# CONTROL.net
KiCad netlist of a schematic drawn in Altium Designer
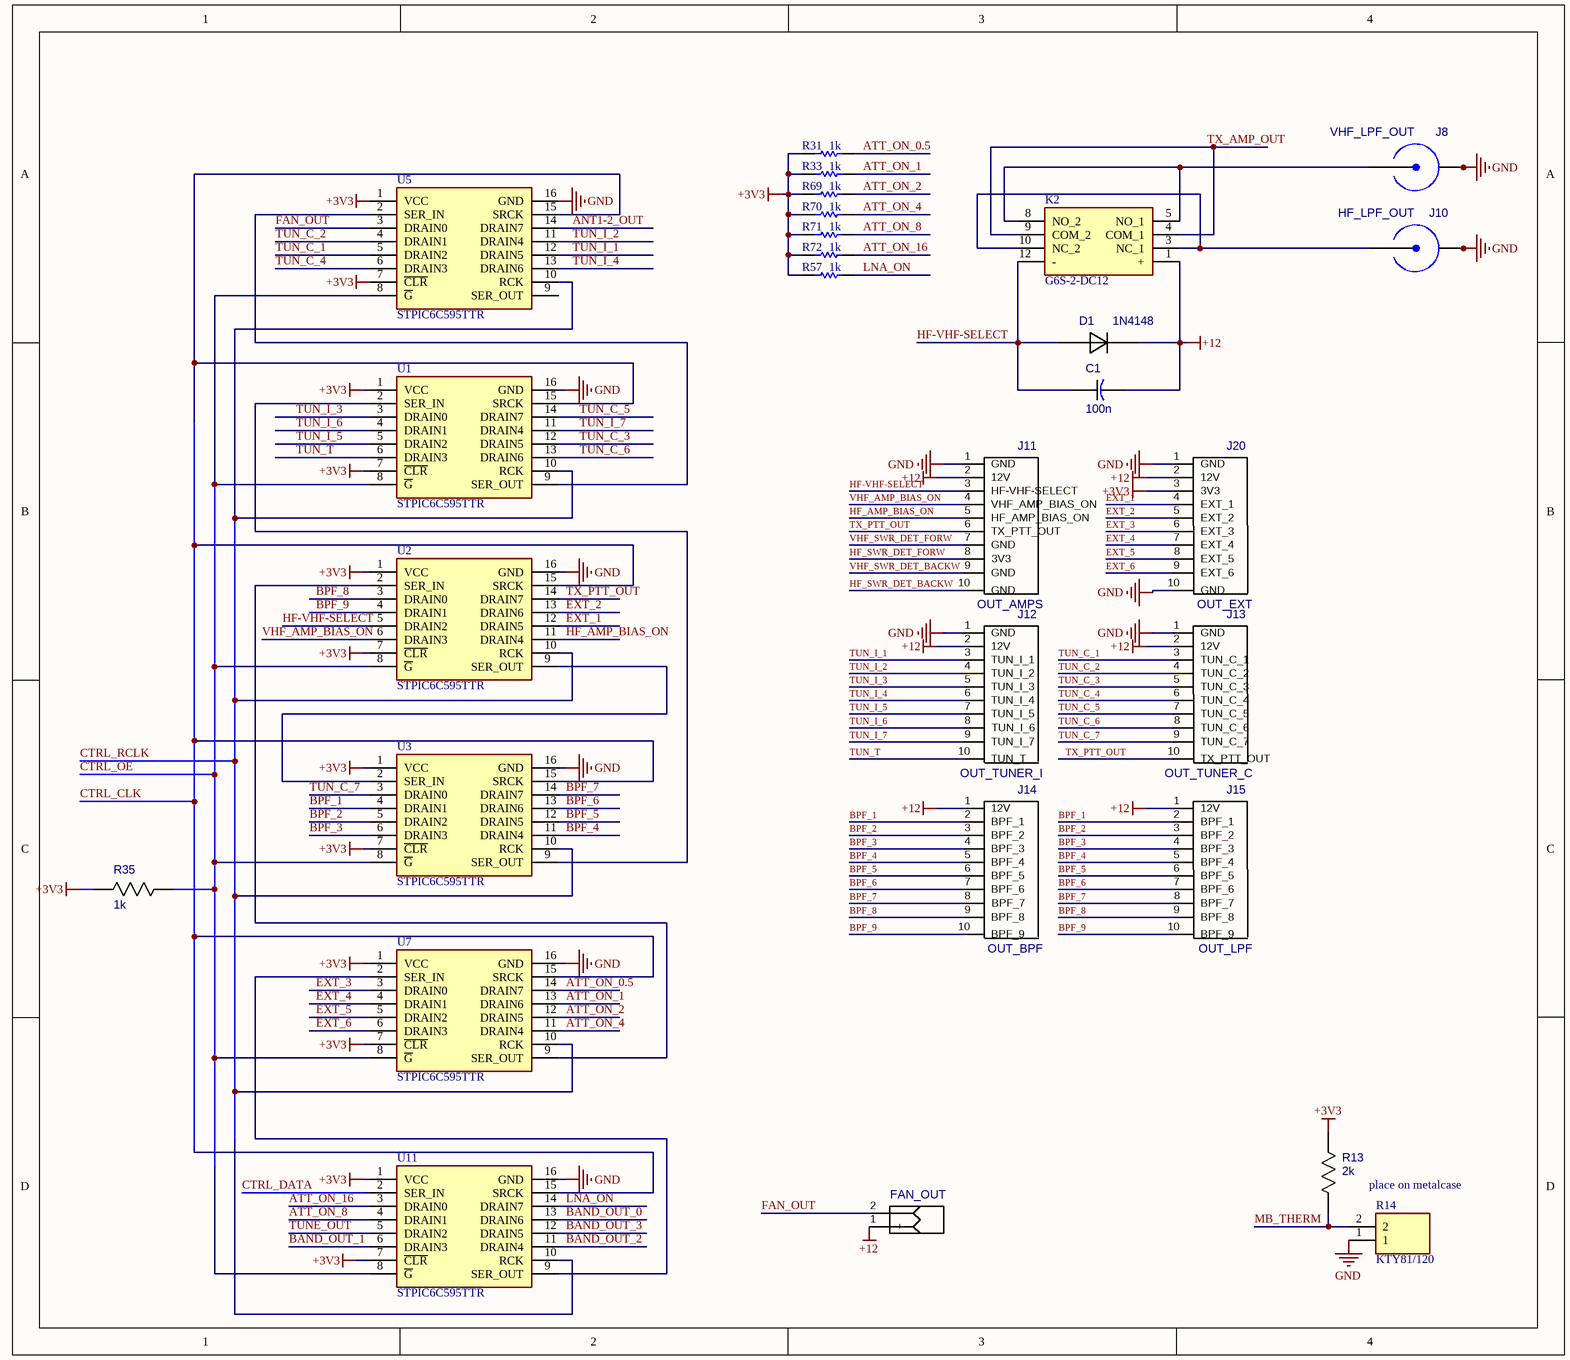
[diagram p0: CONTROL.SchDoc]

(export (version "E")
  (design (tool "Eeschema 10.0.6"))
  (components
    (comp (ref "C1")
      (value "100n")
      (footprint "CAP_0805")
      (description "CAP_0805")
      (libsource (lib "*") (part "CAP_0805"))
    )
    (comp (ref "D1") (value "1N4148") (footprint "SS14") (libsource (lib "RF-UNIT-BIG") (part "1N4148")))
    (comp (ref "FAN_OUT")
      (value "51022-0200")
      (footprint "51022-0200")
      (libsource (lib "*") (part "51022-0200"))
    )
    (comp (ref "J8")
      (value "VHF_LPF_OUT")
      (footprint "31-5431")
      (description "SMA")
      (libsource (lib "RF-UNIT_1") (part "31-5431"))
    )
    (comp (ref "J10")
      (value "HF_LPF_OUT")
      (footprint "31-5431")
      (description "SMA")
      (libsource (lib "RF-UNIT_1") (part "31-5431"))
    )
    (comp (ref "J11")
      (value "OUT_AMPS")
      (footprint "90131-0126")
      (description "2*5 PIN")
      (libsource (lib "RF-UNIT-SPLIT") (part "90131-0126_1_1"))
    )
    (comp (ref "J12")
      (value "OUT_TUNER_I")
      (footprint "90131-0126")
      (description "2*5 PIN")
      (libsource (lib "RF-UNIT-SPLIT") (part "90131-0126_1_1"))
    )
    (comp (ref "J13")
      (value "OUT_TUNER_C")
      (footprint "90131-0126")
      (description "2*5 PIN")
      (libsource (lib "RF-UNIT-SPLIT") (part "90131-0126_1_1"))
    )
    (comp (ref "J14")
      (value "OUT_BPF")
      (footprint "90131-0126")
      (description "2*5 PIN")
      (libsource (lib "RF-UNIT-SPLIT") (part "90131-0126_1_1"))
    )
    (comp (ref "J15")
      (value "OUT_LPF")
      (footprint "90131-0126")
      (description "2*5 PIN")
      (libsource (lib "RF-UNIT-SPLIT") (part "90131-0126_1_1"))
    )
    (comp (ref "J20")
      (value "OUT_EXT")
      (footprint "90131-0126")
      (description "2*5 PIN")
      (libsource (lib "RF-UNIT-SPLIT") (part "90131-0126_1_1"))
    )
    (comp (ref "K2")
      (value "G6S-2-DC12")
      (footprint "G6S2DC12")
      (description "Relay or Contactor")
      (fields (field (name "MOUSER PART NUMBER") "653-G6S-2-DC12A"))
      (libsource (lib "*") (part "G6S-2-DC12"))
    )
    (comp (ref "R13")
      (value "2k")
      (footprint "RES_0805")
      (description "RES_0805")
      (libsource (lib "*") (part "RES_0805"))
    )
    (comp (ref "R14")
      (value "KTY81/120")
      (footprint "TO254P420X460X770-2P")
      (description "Integrated Circuit")
      (fields (field (name "MANUFACTURER_PART_NUMBER") "KTY81/110"))
      (libsource (lib "RF-UNIT-BIG") (part "KTY81_110"))
    )
    (comp (ref "R31")
      (value "1k")
      (footprint "RESC2013X60X40NL20T25")
      (description "RES_0805")
      (fields (field (name "MANUFACTURER") "Panasonic") (field (name "PART NUMBER") "ERA-6AEB303V"))
      (libsource (lib "Altium Content Vault") (part "RES"))
    )
    (comp (ref "R33")
      (value "1k")
      (footprint "RESC2013X60X40NL20T25")
      (description "RES_0805")
      (fields (field (name "MANUFACTURER") "Panasonic") (field (name "PART NUMBER") "ERA-6AEB303V"))
      (libsource (lib "Altium Content Vault") (part "RES"))
    )
    (comp (ref "R35")
      (value "1k")
      (footprint "RES_0805")
      (description "RES_0805")
      (libsource (lib "*") (part "RES_0805"))
    )
    (comp (ref "R57")
      (value "1k")
      (footprint "RESC2013X60X40NL20T25")
      (description "RES_0805")
      (fields (field (name "MANUFACTURER") "Panasonic") (field (name "PART NUMBER") "ERA-6AEB303V"))
      (libsource (lib "Altium Content Vault") (part "RES"))
    )
    (comp (ref "R69")
      (value "1k")
      (footprint "RESC2013X60X40NL20T25")
      (description "RES_0805")
      (fields (field (name "MANUFACTURER") "Panasonic") (field (name "PART NUMBER") "ERA-6AEB303V"))
      (libsource (lib "Altium Content Vault") (part "RES"))
    )
    (comp (ref "R70")
      (value "1k")
      (footprint "RESC2013X60X40NL20T25")
      (description "RES_0805")
      (fields (field (name "MANUFACTURER") "Panasonic") (field (name "PART NUMBER") "ERA-6AEB303V"))
      (libsource (lib "Altium Content Vault") (part "RES"))
    )
    (comp (ref "R71")
      (value "1k")
      (footprint "RESC2013X60X40NL20T25")
      (description "RES_0805")
      (fields (field (name "MANUFACTURER") "Panasonic") (field (name "PART NUMBER") "ERA-6AEB303V"))
      (libsource (lib "Altium Content Vault") (part "RES"))
    )
    (comp (ref "R72")
      (value "1k")
      (footprint "RESC2013X60X40NL20T25")
      (description "RES_0805")
      (fields (field (name "MANUFACTURER") "Panasonic") (field (name "PART NUMBER") "ERA-6AEB303V"))
      (libsource (lib "Altium Content Vault") (part "RES"))
    )
    (comp (ref "U1")
      (value "STPIC6C595TTR")
      (footprint "SOP65P640X120-16N")
      (description "Integrated Circuit")
      (fields (field (name "MOUSER PART NUMBER") "511-STPIC6C595T"))
      (libsource (lib "") (part "STPIC6C595TTR_1"))
    )
    (comp (ref "U2")
      (value "STPIC6C595TTR")
      (footprint "SOP65P640X120-16N")
      (description "Integrated Circuit")
      (fields (field (name "MOUSER PART NUMBER") "511-STPIC6C595T"))
      (libsource (lib "*") (part "STPIC6C595TTR"))
    )
    (comp (ref "U3")
      (value "STPIC6C595TTR")
      (footprint "SOP65P640X120-16N")
      (description "Integrated Circuit")
      (fields (field (name "MOUSER PART NUMBER") "511-STPIC6C595T"))
      (libsource (lib "*") (part "STPIC6C595TTR"))
    )
    (comp (ref "U5")
      (value "STPIC6C595TTR")
      (footprint "SOP65P640X120-16N")
      (description "Integrated Circuit")
      (fields (field (name "MOUSER PART NUMBER") "511-STPIC6C595T"))
      (libsource (lib "") (part "STPIC6C595TTR_1"))
    )
    (comp (ref "U7")
      (value "STPIC6C595TTR")
      (footprint "SOP65P640X120-16N")
      (description "Integrated Circuit")
      (fields (field (name "MOUSER PART NUMBER") "511-STPIC6C595T"))
      (libsource (lib "*") (part "STPIC6C595TTR"))
    )
    (comp (ref "U11")
      (value "STPIC6C595TTR")
      (footprint "SOP65P640X120-16N")
      (description "Integrated Circuit")
      (fields (field (name "MOUSER PART NUMBER") "511-STPIC6C595T"))
      (libsource (lib "*") (part "STPIC6C595TTR"))
    )
  )
  (nets
    (net (code "1") (name "+3V3") (class "Default")
      (node (ref "J20") (pin "3") (pinfunction "3V3_3") (pintype "passive"))
      (node (ref "R13") (pin "2") (pinfunction "2_2") (pintype "passive"))
      (node (ref "R31") (pin "2") (pinfunction "2_2") (pintype "passive"))
      (node (ref "R33") (pin "2") (pinfunction "2_2") (pintype "passive"))
      (node (ref "R35") (pin "1") (pinfunction "1_1") (pintype "passive"))
      (node (ref "R57") (pin "2") (pinfunction "2_2") (pintype "passive"))
      (node (ref "R69") (pin "2") (pinfunction "2_2") (pintype "passive"))
      (node (ref "R70") (pin "2") (pinfunction "2_2") (pintype "passive"))
      (node (ref "R71") (pin "2") (pinfunction "2_2") (pintype "passive"))
      (node (ref "R72") (pin "2") (pinfunction "2_2") (pintype "passive"))
      (node (ref "U1") (pin "1") (pinfunction "VCC_1") (pintype "passive"))
      (node (ref "U1") (pin "7") (pinfunction "~{CLR}_7") (pintype "passive"))
      (node (ref "U11") (pin "1") (pinfunction "VCC_1") (pintype "passive"))
      (node (ref "U11") (pin "7") (pinfunction "~{CLR}_7") (pintype "passive"))
      (node (ref "U2") (pin "1") (pinfunction "VCC_1") (pintype "passive"))
      (node (ref "U2") (pin "7") (pinfunction "~{CLR}_7") (pintype "passive"))
      (node (ref "U3") (pin "1") (pinfunction "VCC_1") (pintype "passive"))
      (node (ref "U3") (pin "7") (pinfunction "~{CLR}_7") (pintype "passive"))
      (node (ref "U5") (pin "1") (pinfunction "VCC_1") (pintype "passive"))
      (node (ref "U5") (pin "7") (pinfunction "~{CLR}_7") (pintype "passive"))
      (node (ref "U7") (pin "1") (pinfunction "VCC_1") (pintype "passive"))
      (node (ref "U7") (pin "7") (pinfunction "~{CLR}_7") (pintype "passive"))
    )
    (net (code "2") (name "+12") (class "Default")
      (node (ref "C1") (pin "2") (pinfunction "2_2") (pintype "passive"))
      (node (ref "D1") (pin "1") (pinfunction "K_1") (pintype "passive"))
      (node (ref "FAN_OUT") (pin "1") (pinfunction "+_1") (pintype "passive"))
      (node (ref "J11") (pin "2") (pinfunction "12V_2") (pintype "passive"))
      (node (ref "J12") (pin "2") (pinfunction "12V_2") (pintype "passive"))
      (node (ref "J13") (pin "2") (pinfunction "12V_2") (pintype "passive"))
      (node (ref "J14") (pin "1") (pinfunction "GND_1") (pintype "passive"))
      (node (ref "J15") (pin "1") (pinfunction "GND_1") (pintype "passive"))
      (node (ref "J20") (pin "2") (pinfunction "12V_2") (pintype "passive"))
      (node (ref "K2") (pin "1") (pinfunction "+_1") (pintype "passive"))
    )
    (net (code "4") (name "/ANT1-2_OUT") (class "Default")
      (node (ref "U5") (pin "14") (pinfunction "DRAIN7_14") (pintype "passive"))
    )
    (net (code "5") (name "/ATT_ON_0.5") (class "Default")
      (node (ref "R31") (pin "1") (pinfunction "1_1") (pintype "passive"))
      (node (ref "U7") (pin "14") (pinfunction "DRAIN7_14") (pintype "passive"))
    )
    (net (code "6") (name "/ATT_ON_1") (class "Default")
      (node (ref "R33") (pin "1") (pinfunction "1_1") (pintype "passive"))
      (node (ref "U7") (pin "13") (pinfunction "DRAIN6_13") (pintype "passive"))
    )
    (net (code "7") (name "/ATT_ON_2") (class "Default")
      (node (ref "R69") (pin "1") (pinfunction "1_1") (pintype "passive"))
      (node (ref "U7") (pin "12") (pinfunction "DRAIN5_12") (pintype "passive"))
    )
    (net (code "8") (name "/ATT_ON_4") (class "Default")
      (node (ref "R70") (pin "1") (pinfunction "1_1") (pintype "passive"))
      (node (ref "U7") (pin "11") (pinfunction "DRAIN4_11") (pintype "passive"))
    )
    (net (code "9") (name "/ATT_ON_8") (class "Default")
      (node (ref "R71") (pin "1") (pinfunction "1_1") (pintype "passive"))
      (node (ref "U11") (pin "4") (pinfunction "DRAIN1_4") (pintype "passive"))
    )
    (net (code "10") (name "/ATT_ON_16") (class "Default")
      (node (ref "R72") (pin "1") (pinfunction "1_1") (pintype "passive"))
      (node (ref "U11") (pin "3") (pinfunction "DRAIN0_3") (pintype "passive"))
    )
    (net (code "11") (name "/BAND_OUT_0") (class "Default")
      (node (ref "U11") (pin "13") (pinfunction "DRAIN6_13") (pintype "passive"))
    )
    (net (code "12") (name "/BAND_OUT_1") (class "Default")
      (node (ref "U11") (pin "6") (pinfunction "DRAIN3_6") (pintype "passive"))
    )
    (net (code "13") (name "/BAND_OUT_2") (class "Default")
      (node (ref "U11") (pin "11") (pinfunction "DRAIN4_11") (pintype "passive"))
    )
    (net (code "14") (name "/BAND_OUT_3") (class "Default")
      (node (ref "U11") (pin "12") (pinfunction "DRAIN5_12") (pintype "passive"))
    )
    (net (code "15") (name "/BPF_1") (class "Default")
      (node (ref "J14") (pin "2") (pinfunction "12V_2") (pintype "passive"))
      (node (ref "J15") (pin "2") (pinfunction "12V_2") (pintype "passive"))
      (node (ref "U3") (pin "4") (pinfunction "DRAIN1_4") (pintype "passive"))
    )
    (net (code "16") (name "/BPF_2") (class "Default")
      (node (ref "J14") (pin "3") (pinfunction "3V3_3") (pintype "passive"))
      (node (ref "J15") (pin "3") (pinfunction "3V3_3") (pintype "passive"))
      (node (ref "U3") (pin "5") (pinfunction "DRAIN2_5") (pintype "passive"))
    )
    (net (code "17") (name "/BPF_3") (class "Default")
      (node (ref "J14") (pin "4") (pinfunction "EXT_1_4") (pintype "passive"))
      (node (ref "J15") (pin "4") (pinfunction "EXT_1_4") (pintype "passive"))
      (node (ref "U3") (pin "6") (pinfunction "DRAIN3_6") (pintype "passive"))
    )
    (net (code "18") (name "/BPF_4") (class "Default")
      (node (ref "J14") (pin "5") (pinfunction "EXT_2_5") (pintype "passive"))
      (node (ref "J15") (pin "5") (pinfunction "EXT_2_5") (pintype "passive"))
      (node (ref "U3") (pin "11") (pinfunction "DRAIN4_11") (pintype "passive"))
    )
    (net (code "19") (name "/BPF_5") (class "Default")
      (node (ref "J14") (pin "6") (pinfunction "EXT_3_6") (pintype "passive"))
      (node (ref "J15") (pin "6") (pinfunction "EXT_3_6") (pintype "passive"))
      (node (ref "U3") (pin "12") (pinfunction "DRAIN5_12") (pintype "passive"))
    )
    (net (code "20") (name "/BPF_6") (class "Default")
      (node (ref "J14") (pin "7") (pinfunction "EXT_4_7") (pintype "passive"))
      (node (ref "J15") (pin "7") (pinfunction "EXT_4_7") (pintype "passive"))
      (node (ref "U3") (pin "13") (pinfunction "DRAIN6_13") (pintype "passive"))
    )
    (net (code "21") (name "/BPF_7") (class "Default")
      (node (ref "J14") (pin "8") (pinfunction "EXT_5_8") (pintype "passive"))
      (node (ref "J15") (pin "8") (pinfunction "EXT_5_8") (pintype "passive"))
      (node (ref "U3") (pin "14") (pinfunction "DRAIN7_14") (pintype "passive"))
    )
    (net (code "22") (name "/BPF_8") (class "Default")
      (node (ref "J14") (pin "9") (pinfunction "EXT_6_9") (pintype "passive"))
      (node (ref "J15") (pin "9") (pinfunction "EXT_6_9") (pintype "passive"))
      (node (ref "U2") (pin "3") (pinfunction "DRAIN0_3") (pintype "passive"))
    )
    (net (code "23") (name "/BPF_9") (class "Default")
      (node (ref "J14") (pin "10") (pinfunction "GND_10") (pintype "passive"))
      (node (ref "J15") (pin "10") (pinfunction "GND_10") (pintype "passive"))
      (node (ref "U2") (pin "4") (pinfunction "DRAIN1_4") (pintype "passive"))
    )
    (net (code "24") (name "/CTRL_CLK") (class "Default")
      (node (ref "U1") (pin "15") (pinfunction "SRCK_15") (pintype "passive"))
      (node (ref "U11") (pin "15") (pinfunction "SRCK_15") (pintype "passive"))
      (node (ref "U2") (pin "15") (pinfunction "SRCK_15") (pintype "passive"))
      (node (ref "U3") (pin "15") (pinfunction "SRCK_15") (pintype "passive"))
      (node (ref "U5") (pin "15") (pinfunction "SRCK_15") (pintype "passive"))
      (node (ref "U7") (pin "15") (pinfunction "SRCK_15") (pintype "passive"))
    )
    (net (code "25") (name "/CTRL_DATA") (class "Default")
      (node (ref "U11") (pin "2") (pinfunction "SER_IN_2") (pintype "passive"))
    )
    (net (code "26") (name "/CTRL_OE") (class "Default")
      (node (ref "R35") (pin "2") (pinfunction "2_2") (pintype "passive"))
      (node (ref "U1") (pin "8") (pinfunction "~{G}_8") (pintype "passive"))
      (node (ref "U11") (pin "8") (pinfunction "~{G}_8") (pintype "passive"))
      (node (ref "U2") (pin "8") (pinfunction "~{G}_8") (pintype "passive"))
      (node (ref "U3") (pin "8") (pinfunction "~{G}_8") (pintype "passive"))
      (node (ref "U5") (pin "8") (pinfunction "~{G}_8") (pintype "passive"))
      (node (ref "U7") (pin "8") (pinfunction "~{G}_8") (pintype "passive"))
    )
    (net (code "27") (name "/CTRL_RCLK") (class "Default")
      (node (ref "U1") (pin "10") (pinfunction "RCK_10") (pintype "passive"))
      (node (ref "U11") (pin "10") (pinfunction "RCK_10") (pintype "passive"))
      (node (ref "U2") (pin "10") (pinfunction "RCK_10") (pintype "passive"))
      (node (ref "U3") (pin "10") (pinfunction "RCK_10") (pintype "passive"))
      (node (ref "U5") (pin "10") (pinfunction "RCK_10") (pintype "passive"))
      (node (ref "U7") (pin "10") (pinfunction "RCK_10") (pintype "passive"))
    )
    (net (code "28") (name "/EXT_1") (class "Default")
      (node (ref "J20") (pin "4") (pinfunction "EXT_1_4") (pintype "passive"))
      (node (ref "U2") (pin "12") (pinfunction "DRAIN5_12") (pintype "passive"))
    )
    (net (code "29") (name "/EXT_2") (class "Default")
      (node (ref "J20") (pin "5") (pinfunction "EXT_2_5") (pintype "passive"))
      (node (ref "U2") (pin "13") (pinfunction "DRAIN6_13") (pintype "passive"))
    )
    (net (code "30") (name "/EXT_3") (class "Default")
      (node (ref "J20") (pin "6") (pinfunction "EXT_3_6") (pintype "passive"))
      (node (ref "U7") (pin "3") (pinfunction "DRAIN0_3") (pintype "passive"))
    )
    (net (code "31") (name "/EXT_4") (class "Default")
      (node (ref "J20") (pin "7") (pinfunction "EXT_4_7") (pintype "passive"))
      (node (ref "U7") (pin "4") (pinfunction "DRAIN1_4") (pintype "passive"))
    )
    (net (code "32") (name "/EXT_5") (class "Default")
      (node (ref "J20") (pin "8") (pinfunction "EXT_5_8") (pintype "passive"))
      (node (ref "U7") (pin "5") (pinfunction "DRAIN2_5") (pintype "passive"))
    )
    (net (code "33") (name "/EXT_6") (class "Default")
      (node (ref "J20") (pin "9") (pinfunction "EXT_6_9") (pintype "passive"))
      (node (ref "U7") (pin "6") (pinfunction "DRAIN3_6") (pintype "passive"))
    )
    (net (code "34") (name "/FAN_OUT") (class "Default")
      (node (ref "FAN_OUT") (pin "2") (pinfunction "-_2") (pintype "passive"))
      (node (ref "U5") (pin "3") (pinfunction "DRAIN0_3") (pintype "passive"))
    )
    (net (code "35") (name "/HF-VHF-SELECT") (class "Default")
      (node (ref "C1") (pin "1") (pinfunction "1_1") (pintype "passive"))
      (node (ref "D1") (pin "2") (pinfunction "A_2") (pintype "passive"))
      (node (ref "J11") (pin "3") (pinfunction "3V3_3") (pintype "passive"))
      (node (ref "K2") (pin "12") (pinfunction "-_12") (pintype "passive"))
      (node (ref "U2") (pin "5") (pinfunction "DRAIN2_5") (pintype "passive"))
    )
    (net (code "36") (name "/HF_AMP_BIAS_ON") (class "Default")
      (node (ref "J11") (pin "5") (pinfunction "EXT_2_5") (pintype "passive"))
      (node (ref "U2") (pin "11") (pinfunction "DRAIN4_11") (pintype "passive"))
    )
    (net (code "37") (name "/HF_SWR_DET_BACKW") (class "Default")
      (node (ref "J11") (pin "10") (pinfunction "GND_10") (pintype "passive"))
    )
    (net (code "38") (name "/HF_SWR_DET_FORW") (class "Default")
      (node (ref "J11") (pin "8") (pinfunction "EXT_5_8") (pintype "passive"))
    )
    (net (code "39") (name "/LNA_ON") (class "Default")
      (node (ref "R57") (pin "1") (pinfunction "1_1") (pintype "passive"))
      (node (ref "U11") (pin "14") (pinfunction "DRAIN7_14") (pintype "passive"))
    )
    (net (code "40") (name "/MB_THERM") (class "Default")
      (node (ref "R13") (pin "1") (pinfunction "1_1") (pintype "passive"))
      (node (ref "R14") (pin "2") (pinfunction "2_2") (pintype "passive"))
    )
    (net (code "41") (name "/TUNE_OUT") (class "Default")
      (node (ref "U11") (pin "5") (pinfunction "DRAIN2_5") (pintype "passive"))
    )
    (net (code "42") (name "/TUN_I_1") (class "Default")
      (node (ref "J12") (pin "3") (pinfunction "3V3_3") (pintype "passive"))
      (node (ref "U5") (pin "12") (pinfunction "DRAIN5_12") (pintype "passive"))
    )
    (net (code "43") (name "/TUN_I_2") (class "Default")
      (node (ref "J12") (pin "4") (pinfunction "EXT_1_4") (pintype "passive"))
      (node (ref "U5") (pin "11") (pinfunction "DRAIN4_11") (pintype "passive"))
    )
    (net (code "44") (name "/TUN_I_3") (class "Default")
      (node (ref "J12") (pin "5") (pinfunction "EXT_2_5") (pintype "passive"))
      (node (ref "U1") (pin "3") (pinfunction "DRAIN0_3") (pintype "passive"))
    )
    (net (code "45") (name "/TUN_I_4") (class "Default")
      (node (ref "J12") (pin "6") (pinfunction "EXT_3_6") (pintype "passive"))
      (node (ref "U5") (pin "13") (pinfunction "DRAIN6_13") (pintype "passive"))
    )
    (net (code "46") (name "/TUN_I_5") (class "Default")
      (node (ref "J12") (pin "7") (pinfunction "EXT_4_7") (pintype "passive"))
      (node (ref "U1") (pin "5") (pinfunction "DRAIN2_5") (pintype "passive"))
    )
    (net (code "47") (name "/TUN_I_6") (class "Default")
      (node (ref "J12") (pin "8") (pinfunction "EXT_5_8") (pintype "passive"))
      (node (ref "U1") (pin "4") (pinfunction "DRAIN1_4") (pintype "passive"))
    )
    (net (code "48") (name "/TUN_I_7") (class "Default")
      (node (ref "J12") (pin "9") (pinfunction "EXT_6_9") (pintype "passive"))
      (node (ref "U1") (pin "11") (pinfunction "DRAIN4_11") (pintype "passive"))
    )
    (net (code "49") (name "/TUN_T") (class "Default")
      (node (ref "J12") (pin "10") (pinfunction "GND_10") (pintype "passive"))
      (node (ref "U1") (pin "6") (pinfunction "DRAIN3_6") (pintype "passive"))
    )
    (net (code "50") (name "/TUN_С_1") (class "Default")
      (node (ref "J13") (pin "3") (pinfunction "3V3_3") (pintype "passive"))
      (node (ref "U5") (pin "5") (pinfunction "DRAIN2_5") (pintype "passive"))
    )
    (net (code "51") (name "/TUN_С_2") (class "Default")
      (node (ref "J13") (pin "4") (pinfunction "EXT_1_4") (pintype "passive"))
      (node (ref "U5") (pin "4") (pinfunction "DRAIN1_4") (pintype "passive"))
    )
    (net (code "52") (name "/TUN_С_3") (class "Default")
      (node (ref "J13") (pin "5") (pinfunction "EXT_2_5") (pintype "passive"))
      (node (ref "U1") (pin "12") (pinfunction "DRAIN5_12") (pintype "passive"))
    )
    (net (code "53") (name "/TUN_С_4") (class "Default")
      (node (ref "J13") (pin "6") (pinfunction "EXT_3_6") (pintype "passive"))
      (node (ref "U5") (pin "6") (pinfunction "DRAIN3_6") (pintype "passive"))
    )
    (net (code "54") (name "/TUN_С_5") (class "Default")
      (node (ref "J13") (pin "7") (pinfunction "EXT_4_7") (pintype "passive"))
      (node (ref "U1") (pin "14") (pinfunction "DRAIN7_14") (pintype "passive"))
    )
    (net (code "55") (name "/TUN_С_6") (class "Default")
      (node (ref "J13") (pin "8") (pinfunction "EXT_5_8") (pintype "passive"))
      (node (ref "U1") (pin "13") (pinfunction "DRAIN6_13") (pintype "passive"))
    )
    (net (code "56") (name "/TUN_С_7") (class "Default")
      (node (ref "J13") (pin "9") (pinfunction "EXT_6_9") (pintype "passive"))
      (node (ref "U3") (pin "3") (pinfunction "DRAIN0_3") (pintype "passive"))
    )
    (net (code "57") (name "/TX_AMP_OUT") (class "Default")
      (node (ref "K2") (pin "4") (pinfunction "COM_1_4") (pintype "passive"))
      (node (ref "K2") (pin "9") (pinfunction "COM_2_9") (pintype "passive"))
    )
    (net (code "58") (name "/TX_PTT_OUT") (class "Default")
      (node (ref "J11") (pin "6") (pinfunction "EXT_3_6") (pintype "passive"))
      (node (ref "J13") (pin "10") (pinfunction "GND_10") (pintype "passive"))
      (node (ref "U2") (pin "14") (pinfunction "DRAIN7_14") (pintype "passive"))
    )
    (net (code "59") (name "/VHF_AMP_BIAS_ON") (class "Default")
      (node (ref "J11") (pin "4") (pinfunction "EXT_1_4") (pintype "passive"))
      (node (ref "U2") (pin "6") (pinfunction "DRAIN3_6") (pintype "passive"))
    )
    (net (code "60") (name "/VHF_SWR_DET_BACKW") (class "Default")
      (node (ref "J11") (pin "9") (pinfunction "EXT_6_9") (pintype "passive"))
    )
    (net (code "61") (name "/VHF_SWR_DET_FORW") (class "Default")
      (node (ref "J11") (pin "7") (pinfunction "EXT_4_7") (pintype "passive"))
    )
    (net (code "62") (name "GND") (class "Default")
      (node (ref "J10") (pin "1") (pinfunction "GND_1") (pintype "passive"))
      (node (ref "J10") (pin "2") (pinfunction "GND_2") (pintype "passive"))
      (node (ref "J10") (pin "3") (pinfunction "GND_3") (pintype "passive"))
      (node (ref "J10") (pin "4") (pinfunction "GND_4") (pintype "passive"))
      (node (ref "J11") (pin "1") (pinfunction "GND_1") (pintype "passive"))
      (node (ref "J12") (pin "1") (pinfunction "GND_1") (pintype "passive"))
      (node (ref "J13") (pin "1") (pinfunction "GND_1") (pintype "passive"))
      (node (ref "J20") (pin "1") (pinfunction "GND_1") (pintype "passive"))
      (node (ref "J20") (pin "10") (pinfunction "GND_10") (pintype "passive"))
      (node (ref "J8") (pin "1") (pinfunction "GND_1") (pintype "passive"))
      (node (ref "J8") (pin "2") (pinfunction "GND_2") (pintype "passive"))
      (node (ref "J8") (pin "3") (pinfunction "GND_3") (pintype "passive"))
      (node (ref "J8") (pin "4") (pinfunction "GND_4") (pintype "passive"))
      (node (ref "R14") (pin "1") (pinfunction "1_1") (pintype "passive"))
      (node (ref "U1") (pin "16") (pinfunction "GND_16") (pintype "passive"))
      (node (ref "U11") (pin "16") (pinfunction "GND_16") (pintype "passive"))
      (node (ref "U2") (pin "16") (pinfunction "GND_16") (pintype "passive"))
      (node (ref "U3") (pin "16") (pinfunction "GND_16") (pintype "passive"))
      (node (ref "U5") (pin "16") (pinfunction "GND_16") (pintype "passive"))
      (node (ref "U7") (pin "16") (pinfunction "GND_16") (pintype "passive"))
    )
    (net (code "63") (name "Net-(J8-CON)") (class "Default")
      (node (ref "J8") (pin "5") (pinfunction "CON_5") (pintype "passive"))
      (node (ref "K2") (pin "5") (pinfunction "NO_1_5") (pintype "passive"))
      (node (ref "K2") (pin "8") (pinfunction "NO_2_8") (pintype "passive"))
    )
    (net (code "64") (name "Net-(J10-CON)") (class "Default")
      (node (ref "J10") (pin "5") (pinfunction "CON_5") (pintype "passive"))
      (node (ref "K2") (pin "10") (pinfunction "NC_2_10") (pintype "passive"))
      (node (ref "K2") (pin "3") (pinfunction "NC_1_3") (pintype "passive"))
    )
    (net (code "65") (name "Net-(U1-SER_IN)") (class "Default")
      (node (ref "U1") (pin "2") (pinfunction "SER_IN_2") (pintype "passive"))
      (node (ref "U3") (pin "9") (pinfunction "SER_OUT_9") (pintype "passive"))
    )
    (net (code "66") (name "Net-(U1-SER_OUT)") (class "Default")
      (node (ref "U1") (pin "9") (pinfunction "SER_OUT_9") (pintype "passive"))
      (node (ref "U5") (pin "2") (pinfunction "SER_IN_2") (pintype "passive"))
    )
    (net (code "67") (name "Net-(U2-SER_IN)") (class "Default")
      (node (ref "U2") (pin "2") (pinfunction "SER_IN_2") (pintype "passive"))
      (node (ref "U7") (pin "9") (pinfunction "SER_OUT_9") (pintype "passive"))
    )
    (net (code "68") (name "Net-(U2-SER_OUT)") (class "Default")
      (node (ref "U2") (pin "9") (pinfunction "SER_OUT_9") (pintype "passive"))
      (node (ref "U3") (pin "2") (pinfunction "SER_IN_2") (pintype "passive"))
    )
    (net (code "69") (name "Net-(U11-SER_OUT)") (class "Default")
      (node (ref "U11") (pin "9") (pinfunction "SER_OUT_9") (pintype "passive"))
      (node (ref "U7") (pin "2") (pinfunction "SER_IN_2") (pintype "passive"))
    )
    (net (code "70") (name "unconnected-(U5-SER_OUT-Pad9)") (class "Default")
      (node (ref "U5") (pin "9") (pinfunction "SER_OUT_9") (pintype "passive"))
    )
  )
)
